# Uart-to-rs232.net
KiCad netlist of a schematic drawn in EAGLE
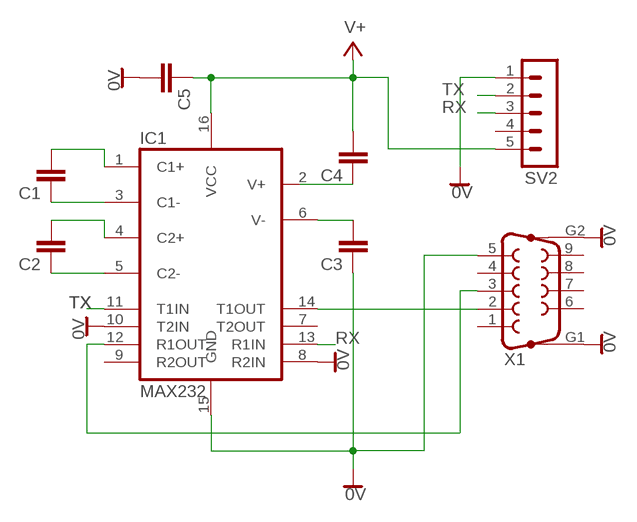
[diagram p0: schematic, sheet 1]

(export (version "E")
  (design (tool "Eeschema 10.0.6"))
  (components
    (comp (ref "C1")
      (value "C0805")
      (footprint "eagle-import:C0805D")
      (libsource (lib "eagle-import") (part "C0805"))
    )
    (comp (ref "C2")
      (value "C0805")
      (footprint "eagle-import:C0805D")
      (libsource (lib "eagle-import") (part "C0805"))
    )
    (comp (ref "C3")
      (value "C0805")
      (footprint "eagle-import:C0805D")
      (libsource (lib "eagle-import") (part "C0805"))
    )
    (comp (ref "C4")
      (value "C0805")
      (footprint "eagle-import:C0805D")
      (libsource (lib "eagle-import") (part "C0805"))
    )
    (comp (ref "C5")
      (value "C0805")
      (footprint "eagle-import:C0805D")
      (libsource (lib "eagle-import") (part "C0805"))
    )
    (comp (ref "IC1")
      (value "MAX232")
      (footprint "eagle-import:DIL16")
      (libsource (lib "eagle-import") (part "MAX232"))
    )
    (comp (ref "SV2")
      (value "MA05-1")
      (footprint "eagle-import:MA05-1")
      (libsource (lib "eagle-import") (part "MA05-1"))
    )
    (comp (ref "X1")
      (value "F09HP")
      (footprint "eagle-import:F09HP")
      (libsource (lib "eagle-import") (part "F09HP"))
    )
  )
  (nets
    (net (code "1") (name "/RX") (class "Default")
      (node (ref "IC1") (pin "13") (pinfunction "R1IN_13") (pintype "input"))
      (node (ref "SV2") (pin "3") (pinfunction "3_3") (pintype "passive"))
    )
    (net (code "2") (name "/TX") (class "Default")
      (node (ref "IC1") (pin "11") (pinfunction "T1IN_11") (pintype "input"))
      (node (ref "SV2") (pin "2") (pinfunction "2_2") (pintype "passive"))
    )
    (net (code "3") (name "0V") (class "Default")
      (node (ref "C3") (pin "1") (pinfunction "1_1") (pintype "passive"))
      (node (ref "C5") (pin "2") (pinfunction "2_2") (pintype "passive"))
      (node (ref "IC1") (pin "10") (pinfunction "T2IN_10") (pintype "input"))
      (node (ref "IC1") (pin "15") (pinfunction "GND_15") (pintype "bidirectional"))
      (node (ref "IC1") (pin "8") (pinfunction "R2IN_8") (pintype "input"))
      (node (ref "SV2") (pin "1") (pinfunction "1_1") (pintype "passive"))
      (node (ref "X1") (pin "5") (pinfunction "5_5") (pintype "passive"))
      (node (ref "X1") (pin "G1") (pinfunction "G1_G1") (pintype "passive"))
      (node (ref "X1") (pin "G2") (pinfunction "G2_G2") (pintype "passive"))
    )
    (net (code "4") (name "Net-(IC1-C1+)") (class "Default")
      (node (ref "C1") (pin "2") (pinfunction "2_2") (pintype "passive"))
      (node (ref "IC1") (pin "1") (pinfunction "C1+_1") (pintype "bidirectional"))
    )
    (net (code "5") (name "Net-(IC1-C1-)") (class "Default")
      (node (ref "C1") (pin "1") (pinfunction "1_1") (pintype "passive"))
      (node (ref "IC1") (pin "3") (pinfunction "C1-_3") (pintype "bidirectional"))
    )
    (net (code "6") (name "Net-(IC1-C2+)") (class "Default")
      (node (ref "C2") (pin "2") (pinfunction "2_2") (pintype "passive"))
      (node (ref "IC1") (pin "4") (pinfunction "C2+_4") (pintype "bidirectional"))
    )
    (net (code "7") (name "Net-(IC1-C2-)") (class "Default")
      (node (ref "C2") (pin "1") (pinfunction "1_1") (pintype "passive"))
      (node (ref "IC1") (pin "5") (pinfunction "C2-_5") (pintype "bidirectional"))
    )
    (net (code "8") (name "Net-(IC1-R1OUT)") (class "Default")
      (node (ref "IC1") (pin "12") (pinfunction "R1OUT_12") (pintype "output"))
      (node (ref "X1") (pin "3") (pinfunction "3_3") (pintype "passive"))
    )
    (net (code "9") (name "Net-(IC1-T1OUT)") (class "Default")
      (node (ref "IC1") (pin "14") (pinfunction "T1OUT_14") (pintype "output"))
      (node (ref "X1") (pin "2") (pinfunction "2_2") (pintype "passive"))
    )
    (net (code "10") (name "Net-(IC1-V+)") (class "Default")
      (node (ref "C4") (pin "1") (pinfunction "1_1") (pintype "passive"))
      (node (ref "IC1") (pin "2") (pinfunction "V+_2") (pintype "bidirectional"))
    )
    (net (code "11") (name "Net-(IC1-V-)") (class "Default")
      (node (ref "C3") (pin "2") (pinfunction "2_2") (pintype "passive"))
      (node (ref "IC1") (pin "6") (pinfunction "V-_6") (pintype "bidirectional"))
    )
    (net (code "12") (name "V+") (class "Default")
      (node (ref "C4") (pin "2") (pinfunction "2_2") (pintype "passive"))
      (node (ref "C5") (pin "1") (pinfunction "1_1") (pintype "passive"))
      (node (ref "IC1") (pin "16") (pinfunction "VCC_16") (pintype "bidirectional"))
      (node (ref "SV2") (pin "5") (pinfunction "5_5") (pintype "passive"))
    )
    (net (code "13") (name "unconnected-(IC1-R2OUT-Pad9)") (class "Default")
      (node (ref "IC1") (pin "9") (pinfunction "R2OUT_9") (pintype "output"))
    )
    (net (code "14") (name "unconnected-(IC1-T2OUT-Pad7)") (class "Default")
      (node (ref "IC1") (pin "7") (pinfunction "T2OUT_7") (pintype "output"))
    )
    (net (code "15") (name "unconnected-(SV2-Pad4)") (class "Default")
      (node (ref "SV2") (pin "4") (pinfunction "4_4") (pintype "passive"))
    )
    (net (code "16") (name "unconnected-(X1-Pad1)") (class "Default")
      (node (ref "X1") (pin "1") (pinfunction "1_1") (pintype "passive"))
    )
    (net (code "17") (name "unconnected-(X1-Pad4)") (class "Default")
      (node (ref "X1") (pin "4") (pinfunction "4_4") (pintype "passive"))
    )
    (net (code "18") (name "unconnected-(X1-Pad6)") (class "Default")
      (node (ref "X1") (pin "6") (pinfunction "6_6") (pintype "passive"))
    )
    (net (code "19") (name "unconnected-(X1-Pad7)") (class "Default")
      (node (ref "X1") (pin "7") (pinfunction "7_7") (pintype "passive"))
    )
    (net (code "20") (name "unconnected-(X1-Pad8)") (class "Default")
      (node (ref "X1") (pin "8") (pinfunction "8_8") (pintype "passive"))
    )
    (net (code "21") (name "unconnected-(X1-Pad9)") (class "Default")
      (node (ref "X1") (pin "9") (pinfunction "9_9") (pintype "passive"))
    )
  )
)
